# PowerCircuit_24V.net
KiCad netlist of a schematic drawn in Altium Designer
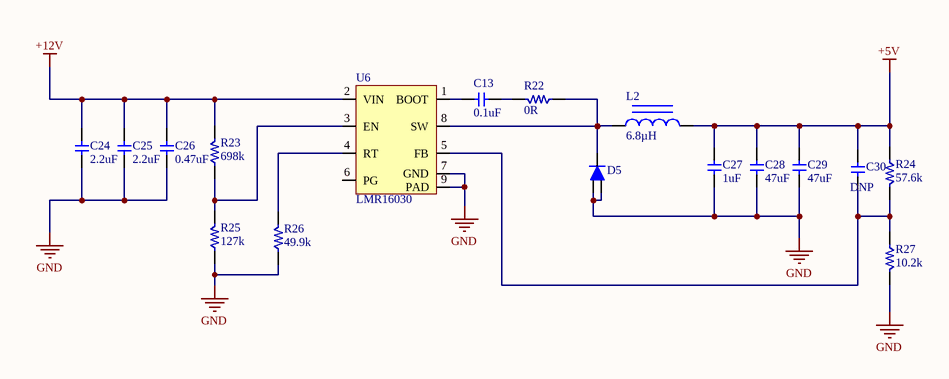
[diagram p0: PowerCircuit_24V.SchDoc]

(export (version "E")
  (design (tool "Eeschema 10.0.6"))
  (components
    (comp (ref "C13")
      (value "0.1uF")
      (footprint "0603")
      (description "Generic capacitor")
      (fields (field (name "Comment") "Generic Capacitor"))
      (libsource (lib "PowerCircuit") (part "Capacitor"))
    )
    (comp (ref "C24")
      (value "2.2uF")
      (footprint "Cap 1210")
      (description "Generic capacitor")
      (fields (field (name "Comment") "Generic Capacitor"))
      (libsource (lib "PowerCircuit") (part "Capacitor"))
    )
    (comp (ref "C25")
      (value "2.2uF")
      (footprint "Cap 1210")
      (description "Generic capacitor")
      (fields (field (name "Comment") "Generic Capacitor"))
      (libsource (lib "PowerCircuit") (part "Capacitor"))
    )
    (comp (ref "C26")
      (value "0.47uF")
      (footprint "0805")
      (description "Generic capacitor")
      (fields (field (name "Comment") "Generic Capacitor"))
      (libsource (lib "PowerCircuit") (part "Capacitor"))
    )
    (comp (ref "C27")
      (value "1uF")
      (footprint "0805")
      (description "Generic capacitor")
      (fields (field (name "Comment") "Generic Capacitor"))
      (libsource (lib "PowerCircuit") (part "Capacitor"))
    )
    (comp (ref "C28")
      (value "47uF")
      (footprint "Cap 1210")
      (description "Generic capacitor")
      (fields (field (name "Comment") "Generic Capacitor"))
      (libsource (lib "PowerCircuit") (part "Capacitor"))
    )
    (comp (ref "C29")
      (value "47uF")
      (footprint "Cap 1210")
      (description "Generic capacitor")
      (fields (field (name "Comment") "Generic Capacitor"))
      (libsource (lib "PowerCircuit") (part "Capacitor"))
    )
    (comp (ref "C30")
      (value "Generic Capacitor")
      (footprint "0603")
      (description "Generic capacitor")
      (fields (field (name "DIGIKEY") "DNP"))
      (libsource (lib "PowerCircuit") (part "Capacitor"))
    )
    (comp (ref "D5")
      (value "DIODE SCHOTTKY 60V 5A")
      (footprint "TO277A")
      (description "DIODE SCHOTTKY 60V 5A TO277A")
      (fields
        (field (name "MANUFACTURER") "Vishay Semiconductor Diodes Division")
        (field (name "MANUFACTURER PART NUMBER") "SS5P6-M3/86A")
      )
      (libsource (lib "PowerCircuit") (part "SS5P6-M3/86A"))
    )
    (comp (ref "L2")
      (value "FIXED IND 6.8UH 5.2A")
      (footprint "7447714068")
      (description "FIXED IND 6.8UH 5.2A 22 MOHM SMD")
      (fields
        (field (name "MANUFACTURER") "Wurth Electronics Inc.")
        (field (name "MANUFACTURER PART NUMBER") "7447714068")
        (field (name "INDUCTANCE") "6.8µH")
      )
      (libsource (lib "PowerCircuit") (part "7447714068"))
    )
    (comp (ref "R22")
      (value "0R")
      (footprint "0603")
      (description "Generic Resistor")
      (fields (field (name "Comment") "Resistor"))
      (libsource (lib "PowerCircuit") (part "Resistor"))
    )
    (comp (ref "R23")
      (value "698k")
      (footprint "0603")
      (description "Generic Resistor")
      (fields (field (name "Comment") "Resistor"))
      (libsource (lib "PowerCircuit") (part "Resistor"))
    )
    (comp (ref "R24")
      (value "57.6k")
      (footprint "0603")
      (description "Generic Resistor")
      (fields (field (name "Comment") "Resistor"))
      (libsource (lib "PowerCircuit") (part "Resistor"))
    )
    (comp (ref "R25")
      (value "127k")
      (footprint "0603")
      (description "Generic Resistor")
      (fields (field (name "Comment") "Resistor"))
      (libsource (lib "PowerCircuit") (part "Resistor"))
    )
    (comp (ref "R26")
      (value "49.9k")
      (footprint "0603")
      (description "Generic Resistor")
      (fields (field (name "Comment") "Resistor"))
      (libsource (lib "PowerCircuit") (part "Resistor"))
    )
    (comp (ref "R27")
      (value "10.2k")
      (footprint "0603")
      (description "Generic Resistor")
      (fields (field (name "Comment") "Resistor"))
      (libsource (lib "PowerCircuit") (part "Resistor"))
    )
    (comp (ref "U6")
      (value "LMR16030")
      (footprint "LMR16030")
      (description "IC REG BUCK ADJ 3A 8SOPWRPD")
      (fields
        (field (name "MANUFACTURER") "Texas Instruments")
        (field (name "MANUFACTURER PART NUMBER") "LMR16030PDDA")
      )
      (libsource (lib "PowerCircuit") (part "LMR16030"))
    )
  )
  (nets
    (net (code "1") (name "+5V") (class "Default")
      (node (ref "C27") (pin "1") (pinfunction "1_1") (pintype "passive"))
      (node (ref "C28") (pin "1") (pinfunction "1_1") (pintype "passive"))
      (node (ref "C29") (pin "1") (pinfunction "1_1") (pintype "passive"))
      (node (ref "C30") (pin "1") (pinfunction "1_1") (pintype "passive"))
      (node (ref "L2") (pin "0") (pinfunction "0_0") (pintype "passive"))
      (node (ref "R24") (pin "1") (pinfunction "1_1") (pintype "passive"))
    )
    (net (code "2") (name "+12V") (class "Default")
      (node (ref "C24") (pin "1") (pinfunction "1_1") (pintype "passive"))
      (node (ref "C25") (pin "1") (pinfunction "1_1") (pintype "passive"))
      (node (ref "C26") (pin "1") (pinfunction "1_1") (pintype "passive"))
      (node (ref "R23") (pin "2") (pinfunction "2_2") (pintype "passive"))
      (node (ref "U6") (pin "2") (pinfunction "VIN_2") (pintype "passive"))
    )
    (net (code "3") (name "GND") (class "Default")
      (node (ref "C24") (pin "2") (pinfunction "2_2") (pintype "passive"))
      (node (ref "C25") (pin "2") (pinfunction "2_2") (pintype "passive"))
      (node (ref "C26") (pin "2") (pinfunction "2_2") (pintype "passive"))
      (node (ref "C27") (pin "2") (pinfunction "2_2") (pintype "passive"))
      (node (ref "C28") (pin "2") (pinfunction "2_2") (pintype "passive"))
      (node (ref "C29") (pin "2") (pinfunction "2_2") (pintype "passive"))
      (node (ref "D5") (pin "1") (pinfunction "1_1") (pintype "passive"))
      (node (ref "D5") (pin "2") (pinfunction "2_2") (pintype "passive"))
      (node (ref "R25") (pin "1") (pinfunction "1_1") (pintype "passive"))
      (node (ref "R26") (pin "1") (pinfunction "1_1") (pintype "passive"))
      (node (ref "R27") (pin "2") (pinfunction "2_2") (pintype "passive"))
      (node (ref "U6") (pin "7") (pinfunction "GND_7") (pintype "passive"))
      (node (ref "U6") (pin "9") (pinfunction "PAD_9") (pintype "passive"))
    )
    (net (code "4") (name "Net-(C13-Pad2)") (class "Default")
      (node (ref "C13") (pin "2") (pinfunction "2_2") (pintype "passive"))
      (node (ref "R22") (pin "2") (pinfunction "2_2") (pintype "passive"))
    )
    (net (code "5") (name "Net-(U6-BOOT)") (class "Default")
      (node (ref "C13") (pin "1") (pinfunction "1_1") (pintype "passive"))
      (node (ref "U6") (pin "1") (pinfunction "BOOT_1") (pintype "passive"))
    )
    (net (code "6") (name "Net-(U6-EN)") (class "Default")
      (node (ref "R23") (pin "1") (pinfunction "1_1") (pintype "passive"))
      (node (ref "R25") (pin "2") (pinfunction "2_2") (pintype "passive"))
      (node (ref "U6") (pin "3") (pinfunction "EN_3") (pintype "passive"))
    )
    (net (code "7") (name "Net-(U6-FB)") (class "Default")
      (node (ref "C30") (pin "2") (pinfunction "2_2") (pintype "passive"))
      (node (ref "R24") (pin "2") (pinfunction "2_2") (pintype "passive"))
      (node (ref "R27") (pin "1") (pinfunction "1_1") (pintype "passive"))
      (node (ref "U6") (pin "5") (pinfunction "FB_5") (pintype "passive"))
    )
    (net (code "8") (name "Net-(U6-RT)") (class "Default")
      (node (ref "R26") (pin "2") (pinfunction "2_2") (pintype "passive"))
      (node (ref "U6") (pin "4") (pinfunction "RT_4") (pintype "passive"))
    )
    (net (code "9") (name "Net-(U6-SW)") (class "Default")
      (node (ref "D5") (pin "3") (pinfunction "3_3") (pintype "passive"))
      (node (ref "L2") (pin "1") (pinfunction "1_1") (pintype "passive"))
      (node (ref "R22") (pin "1") (pinfunction "1_1") (pintype "passive"))
      (node (ref "U6") (pin "8") (pinfunction "SW_8") (pintype "passive"))
    )
    (net (code "10") (name "unconnected-(U6-PG-Pad6)") (class "Default")
      (node (ref "U6") (pin "6") (pinfunction "PG_6") (pintype "passive"))
    )
  )
)
